# Signal_Turn_D_41mm.net
KiCad netlist of a schematic drawn in Altium Designer
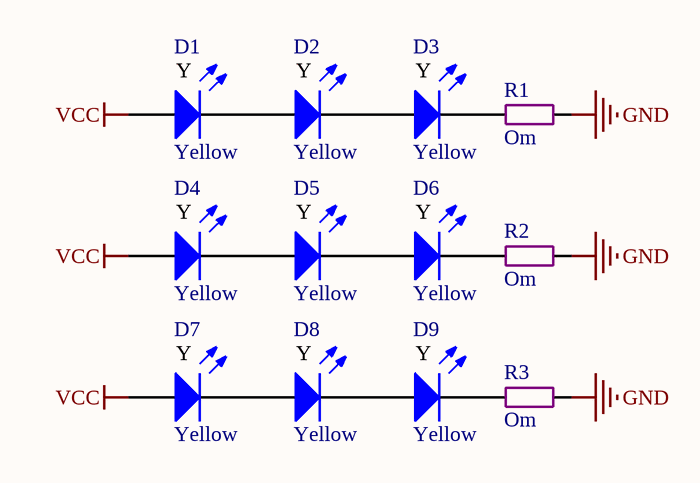
[diagram p0: Signal Turn D 41mm.SchDoc]

(export (version "E")
  (design (tool "Eeschema 10.0.6"))
  (components
    (comp (ref "D1")
      (value "Yellow")
      (footprint "LED:LED Round 8mm Yellow")
      (description "2.8-3v 25mA, 4-5cd")
      (libsource (lib "LED") (part "Led Round 8mm Yellow 0.5W"))
    )
    (comp (ref "D2")
      (value "Yellow")
      (footprint "LED:LED Round 8mm Yellow")
      (description "2.8-3v 25mA, 4-5cd")
      (libsource (lib "LED") (part "Led Round 8mm Yellow 0.5W"))
    )
    (comp (ref "D3")
      (value "Yellow")
      (footprint "LED:LED Round 8mm Yellow")
      (description "2.8-3v 25mA, 4-5cd")
      (libsource (lib "LED") (part "Led Round 8mm Yellow 0.5W"))
    )
    (comp (ref "D4")
      (value "Yellow")
      (footprint "LED:LED Round 8mm Yellow")
      (description "2.8-3v 25mA, 4-5cd")
      (libsource (lib "LED") (part "Led Round 8mm Yellow 0.5W"))
    )
    (comp (ref "D5")
      (value "Yellow")
      (footprint "LED:LED Round 8mm Yellow")
      (description "2.8-3v 25mA, 4-5cd")
      (libsource (lib "LED") (part "Led Round 8mm Yellow 0.5W"))
    )
    (comp (ref "D6")
      (value "Yellow")
      (footprint "LED:LED Round 8mm Yellow")
      (description "2.8-3v 25mA, 4-5cd")
      (libsource (lib "LED") (part "Led Round 8mm Yellow 0.5W"))
    )
    (comp (ref "D7")
      (value "Yellow")
      (footprint "LED:LED Round 8mm Yellow")
      (description "2.8-3v 25mA, 4-5cd")
      (libsource (lib "LED") (part "Led Round 8mm Yellow 0.5W"))
    )
    (comp (ref "D8")
      (value "Yellow")
      (footprint "LED:LED Round 8mm Yellow")
      (description "2.8-3v 25mA, 4-5cd")
      (libsource (lib "LED") (part "Led Round 8mm Yellow 0.5W"))
    )
    (comp (ref "D9")
      (value "Yellow")
      (footprint "LED:LED Round 8mm Yellow")
      (description "2.8-3v 25mA, 4-5cd")
      (libsource (lib "LED") (part "Led Round 8mm Yellow 0.5W"))
    )
    (comp (ref "R1")
      (value "Om")
      (footprint "PassiveComponents:Res p20.32 (9p) 2w")
      (description "5W Cement")
      (libsource (lib "PassiveComponents") (part "Res 2W"))
    )
    (comp (ref "R2")
      (value "Om")
      (footprint "PassiveComponents:Res p20.32 (9p) 2w")
      (description "5W Cement")
      (libsource (lib "PassiveComponents") (part "Res 2W"))
    )
    (comp (ref "R3")
      (value "Om")
      (footprint "PassiveComponents:Res p20.32 (9p) 2w")
      (description "5W Cement")
      (libsource (lib "PassiveComponents") (part "Res 2W"))
    )
  )
  (nets
    (net (code "1") (name "GND") (class "Default")
      (node (ref "R1") (pin "2") (pinfunction "2_2") (pintype "passive"))
      (node (ref "R2") (pin "2") (pinfunction "2_2") (pintype "passive"))
      (node (ref "R3") (pin "2") (pinfunction "2_2") (pintype "passive"))
    )
    (net (code "2") (name "Net-(D1-PadK)") (class "Default")
      (node (ref "D1") (pin "K") (pinfunction "K_K") (pintype "passive"))
      (node (ref "D2") (pin "A") (pinfunction "A_A") (pintype "passive"))
    )
    (net (code "3") (name "Net-(D2-PadK)") (class "Default")
      (node (ref "D2") (pin "K") (pinfunction "K_K") (pintype "passive"))
      (node (ref "D3") (pin "A") (pinfunction "A_A") (pintype "passive"))
    )
    (net (code "4") (name "Net-(D3-PadK)") (class "Default")
      (node (ref "D3") (pin "K") (pinfunction "K_K") (pintype "passive"))
      (node (ref "R1") (pin "1") (pinfunction "1_1") (pintype "passive"))
    )
    (net (code "5") (name "Net-(D4-PadK)") (class "Default")
      (node (ref "D4") (pin "K") (pinfunction "K_K") (pintype "passive"))
      (node (ref "D5") (pin "A") (pinfunction "A_A") (pintype "passive"))
    )
    (net (code "6") (name "Net-(D5-PadK)") (class "Default")
      (node (ref "D5") (pin "K") (pinfunction "K_K") (pintype "passive"))
      (node (ref "D6") (pin "A") (pinfunction "A_A") (pintype "passive"))
    )
    (net (code "7") (name "Net-(D6-PadK)") (class "Default")
      (node (ref "D6") (pin "K") (pinfunction "K_K") (pintype "passive"))
      (node (ref "R2") (pin "1") (pinfunction "1_1") (pintype "passive"))
    )
    (net (code "8") (name "Net-(D7-PadK)") (class "Default")
      (node (ref "D7") (pin "K") (pinfunction "K_K") (pintype "passive"))
      (node (ref "D8") (pin "A") (pinfunction "A_A") (pintype "passive"))
    )
    (net (code "9") (name "Net-(D8-PadK)") (class "Default")
      (node (ref "D8") (pin "K") (pinfunction "K_K") (pintype "passive"))
      (node (ref "D9") (pin "A") (pinfunction "A_A") (pintype "passive"))
    )
    (net (code "10") (name "Net-(D9-PadK)") (class "Default")
      (node (ref "D9") (pin "K") (pinfunction "K_K") (pintype "passive"))
      (node (ref "R3") (pin "1") (pinfunction "1_1") (pintype "passive"))
    )
    (net (code "11") (name "VCC") (class "Default")
      (node (ref "D1") (pin "A") (pinfunction "A_A") (pintype "passive"))
      (node (ref "D4") (pin "A") (pinfunction "A_A") (pintype "passive"))
      (node (ref "D7") (pin "A") (pinfunction "A_A") (pintype "passive"))
    )
  )
)
